# Kar_IMU.net
KiCad netlist of a schematic drawn in Altium Designer
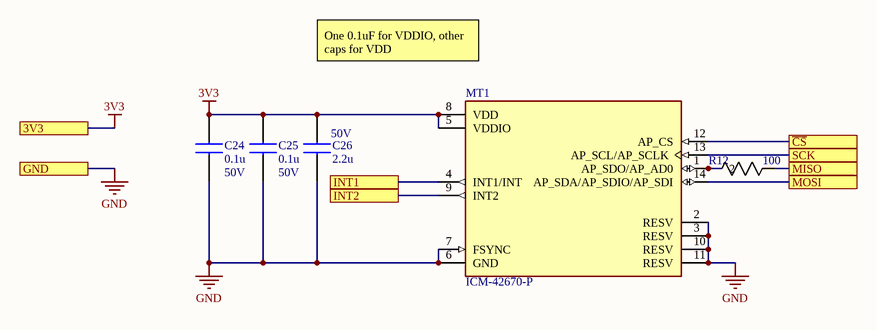
[diagram p0: Kar_IMU.SchDoc]

(export (version "E")
  (design (tool "Eeschema 10.0.6"))
  (components
    (comp (ref "C24")
      (value "0.1u")
      (footprint "CAPC2012X145N")
      (description "Multilayer Ceramic Chip Capacitors, Capacitance=0.1u")
      (fields
        (field (name "MANUFACTURER_PART_NUMBER") "KAM21BR71H104JM")
        (field (name "RATED VOLTAGE") "50V")
      )
      (libsource (lib "Caps") (part "KAM21BR71H104JM"))
    )
    (comp (ref "C25")
      (value "0.1u")
      (footprint "CAPC2012X145N")
      (description "Multilayer Ceramic Chip Capacitors, Capacitance=0.1u")
      (fields
        (field (name "MANUFACTURER_PART_NUMBER") "KAM21BR71H104JM")
        (field (name "RATED VOLTAGE") "50V")
      )
      (libsource (lib "Caps") (part "KAM21BR71H104JM"))
    )
    (comp (ref "C26")
      (value "2.2u")
      (footprint "CAPC2012X145N")
      (description "Multilayer Ceramic Chip Capacitors, Capacitance=2.2u")
      (fields
        (field (name "MANUFACTURER_PART_NUMBER") "C2012X7R1H225K125AE")
        (field (name "RATED VOLTAGE") "50V")
      )
      (libsource (lib "Caps") (part "C2012X7R1H225K125AE"))
    )
    (comp (ref "MT1")
      (value "ICM-42670-P")
      (footprint "XDCR_ICM-42670-P")
      (libsource (lib "ICM-42670-P") (part "ICM-42670-P"))
    )
    (comp (ref "R12")
      (value "100")
      (footprint "RC0805N_YAG")
      (description "RES 0805 100 5% 1/8W")
      (fields (field (name "MANUFACTURER_PART_NUMBER") "RC0805JR-07100RL") (field (name "TOLERANCE") "5%"))
      (libsource (lib "Resistors") (part "RC0805JR-07100RL"))
    )
  )
  (nets
    (net (code "1") (name "/INT1") (class "Default")
      (node (ref "MT1") (pin "4") (pinfunction "INT1/INT_4") (pintype "output"))
    )
    (net (code "2") (name "/INT2") (class "Default")
      (node (ref "MT1") (pin "9") (pinfunction "INT2_9") (pintype "output"))
    )
    (net (code "3") (name "/MISO") (class "Default")
      (node (ref "R12") (pin "1") (pinfunction "1_1") (pintype "passive"))
    )
    (net (code "4") (name "/MOSI") (class "Default")
      (node (ref "MT1") (pin "14") (pinfunction "AP_SDA/AP_SDIO/AP_SDI_14") (pintype "bidirectional"))
    )
    (net (code "5") (name "/SCK") (class "Default")
      (node (ref "MT1") (pin "13") (pinfunction "AP_SCL/AP_SCLK_13") (pintype "input"))
    )
    (net (code "6") (name "/~{CS}") (class "Default")
      (node (ref "MT1") (pin "12") (pinfunction "AP_CS_12") (pintype "input"))
    )
    (net (code "7") (name "3V3") (class "Default")
      (node (ref "C24") (pin "2") (pinfunction "2_2") (pintype "passive"))
      (node (ref "C25") (pin "2") (pinfunction "2_2") (pintype "passive"))
      (node (ref "C26") (pin "2") (pinfunction "2_2") (pintype "passive"))
      (node (ref "MT1") (pin "5") (pinfunction "VDDIO_5") (pintype "power_in"))
      (node (ref "MT1") (pin "8") (pinfunction "VDD_8") (pintype "power_in"))
    )
    (net (code "8") (name "GND") (class "Default")
      (node (ref "C24") (pin "1") (pinfunction "1_1") (pintype "passive"))
      (node (ref "C25") (pin "1") (pinfunction "1_1") (pintype "passive"))
      (node (ref "C26") (pin "1") (pinfunction "1_1") (pintype "passive"))
      (node (ref "MT1") (pin "10") (pinfunction "RESV_10") (pintype "passive"))
      (node (ref "MT1") (pin "11") (pinfunction "RESV_11") (pintype "passive"))
      (node (ref "MT1") (pin "2") (pinfunction "RESV_2") (pintype "passive"))
      (node (ref "MT1") (pin "3") (pinfunction "RESV_3") (pintype "passive"))
      (node (ref "MT1") (pin "6") (pinfunction "GND_6") (pintype "power_in"))
      (node (ref "MT1") (pin "7") (pinfunction "FSYNC_7") (pintype "input"))
    )
    (net (code "9") (name "Net-(MT1-AP_SDO{slash}AP_AD0)") (class "Default")
      (node (ref "MT1") (pin "1") (pinfunction "AP_SDO/AP_AD0_1") (pintype "bidirectional"))
      (node (ref "R12") (pin "2") (pinfunction "2_2") (pintype "passive"))
    )
  )
)
